# LEDDimmerI2C.net
KiCad netlist of a schematic drawn in EAGLE
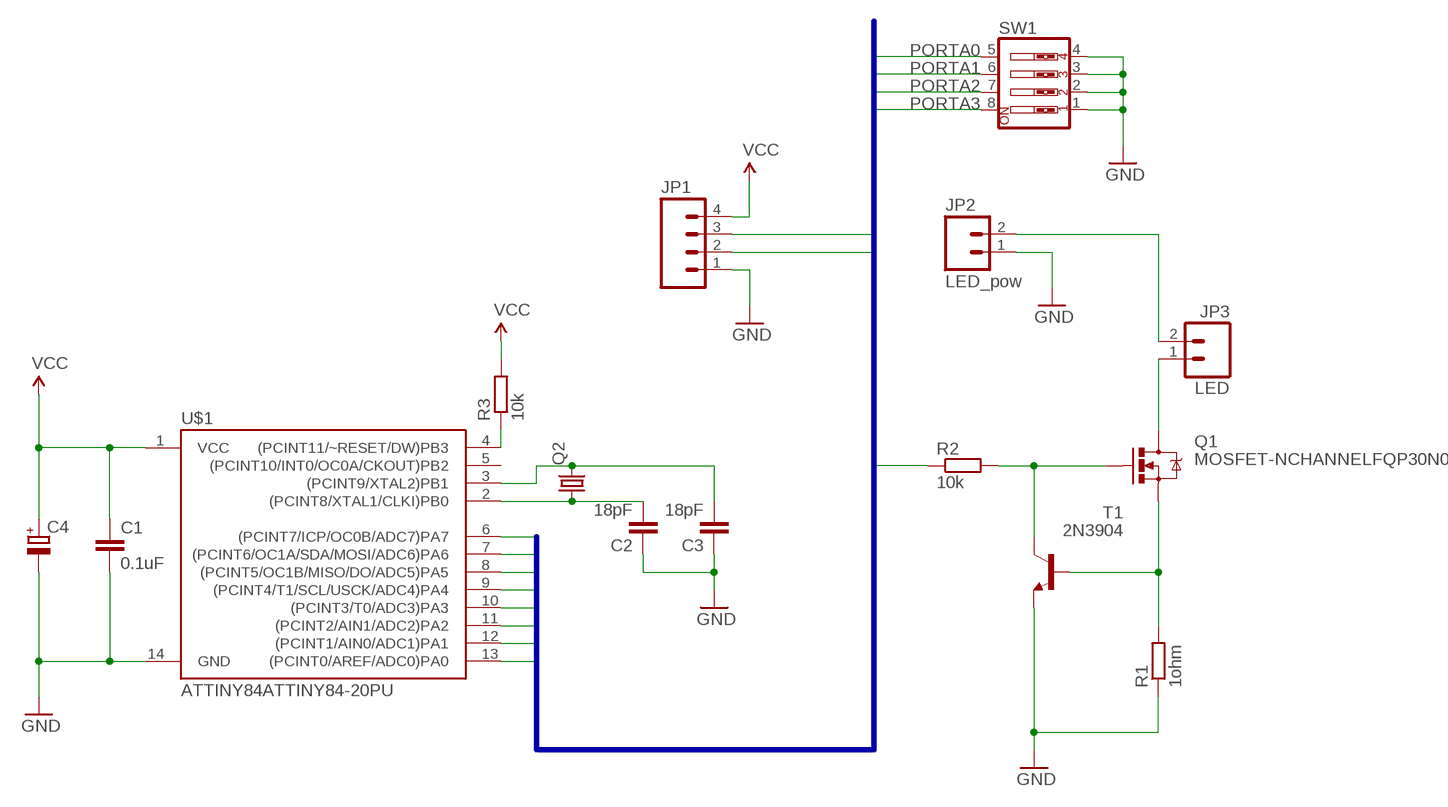
[diagram p0: schematic, sheet 1]

(export (version "E")
  (design (tool "Eeschema 10.0.6"))
  (components
    (comp (ref "C1")
      (value "0.1uF")
      (footprint "eagle-import:0805")
      (libsource (lib "eagle-import") (part "CAP0805"))
    )
    (comp (ref "C2")
      (value "18pF")
      (footprint "eagle-import:0805")
      (libsource (lib "eagle-import") (part "CAP0805"))
    )
    (comp (ref "C3")
      (value "18pF")
      (footprint "eagle-import:0805")
      (libsource (lib "eagle-import") (part "CAP0805"))
    )
    (comp (ref "C4")
      (value "CPOL-EUE3.5-10")
      (footprint "eagle-import:E3,5-10")
      (libsource (lib "eagle-import") (part "CPOL-EUE3.5-10"))
    )
    (comp (ref "JP1")
      (value "M04LONGPADS")
      (footprint "eagle-import:1X04_LONGPADS")
      (libsource (lib "eagle-import") (part "M04LONGPADS"))
    )
    (comp (ref "JP2")
      (value "LED_pow")
      (footprint "eagle-import:1X02_LONGPADS")
      (libsource (lib "eagle-import") (part "M02PTH3"))
    )
    (comp (ref "JP3")
      (value "LED")
      (footprint "eagle-import:1X02_LONGPADS")
      (libsource (lib "eagle-import") (part "M02PTH3"))
    )
    (comp (ref "Q1")
      (value "MOSFET-NCHANNELFQP30N06L")
      (footprint "eagle-import:TO220V")
      (libsource (lib "eagle-import") (part "MOSFET-NCHANNELFQP30N06L"))
    )
    (comp (ref "Q2")
      (value "CRYSTALSM49")
      (footprint "eagle-import:SM49")
      (libsource (lib "eagle-import") (part "CRYSTALSM49"))
    )
    (comp (ref "R1")
      (value "1ohm")
      (footprint "eagle-import:VMTB60")
      (libsource (lib "eagle-import") (part "R-EU_VMTB60"))
    )
    (comp (ref "R2")
      (value "10k")
      (footprint "eagle-import:R0805")
      (libsource (lib "eagle-import") (part "R-EU_R0805"))
    )
    (comp (ref "R3")
      (value "10k")
      (footprint "eagle-import:R0805")
      (libsource (lib "eagle-import") (part "R-EU_R0805"))
    )
    (comp (ref "SW1")
      (value "SW_DIP-4")
      (footprint "eagle-import:EDG-04")
      (libsource (lib "eagle-import") (part "SW_DIP-4"))
    )
    (comp (ref "T1")
      (value "2N3904")
      (footprint "eagle-import:TO92")
      (libsource (lib "eagle-import") (part "2N3904"))
    )
    (comp (ref "U$1")
      (value "ATTINY84ATTINY84-20PU")
      (footprint "eagle-import:DIL14")
      (libsource (lib "eagle-import") (part "ATTINY84ATTINY84-20PU"))
    )
  )
  (nets
    (net (code "1") (name "/PORTA0") (class "Default")
      (node (ref "SW1") (pin "5") (pinfunction "5_5") (pintype "passive"))
      (node (ref "U$1") (pin "13") (pinfunction "(PCINT0/AREF/ADC0)PA0_13") (pintype "bidirectional"))
    )
    (net (code "2") (name "/PORTA1") (class "Default")
      (node (ref "SW1") (pin "6") (pinfunction "6_6") (pintype "passive"))
      (node (ref "U$1") (pin "12") (pinfunction "(PCINT1/AIN0/ADC1)PA1_12") (pintype "bidirectional"))
    )
    (net (code "3") (name "/PORTA2") (class "Default")
      (node (ref "SW1") (pin "7") (pinfunction "7_7") (pintype "passive"))
      (node (ref "U$1") (pin "11") (pinfunction "(PCINT2/AIN1/ADC2)PA2_11") (pintype "bidirectional"))
    )
    (net (code "4") (name "/PORTA3") (class "Default")
      (node (ref "SW1") (pin "8") (pinfunction "8_8") (pintype "passive"))
      (node (ref "U$1") (pin "10") (pinfunction "(PCINT3/T0/ADC3)PA3_10") (pintype "bidirectional"))
    )
    (net (code "5") (name "/PORTA4") (class "Default")
      (node (ref "JP1") (pin "2") (pinfunction "2_2") (pintype "passive"))
      (node (ref "U$1") (pin "9") (pinfunction "(PCINT4/T1/SCL/USCK/ADC4)PA4_9") (pintype "bidirectional"))
    )
    (net (code "6") (name "/PORTA5") (class "Default")
      (node (ref "R2") (pin "1") (pinfunction "1_1") (pintype "passive"))
      (node (ref "U$1") (pin "8") (pinfunction "(PCINT5/OC1B/MISO/DO/ADC5)PA5_8") (pintype "bidirectional"))
    )
    (net (code "7") (name "/PORTA6") (class "Default")
      (node (ref "JP1") (pin "3") (pinfunction "3_3") (pintype "passive"))
      (node (ref "U$1") (pin "7") (pinfunction "(PCINT6/OC1A/SDA/MOSI/ADC6)PA6_7") (pintype "bidirectional"))
    )
    (net (code "8") (name "GND") (class "Default")
      (node (ref "C1") (pin "2") (pinfunction "2_2") (pintype "passive"))
      (node (ref "C2") (pin "1") (pinfunction "1_1") (pintype "passive"))
      (node (ref "C3") (pin "1") (pinfunction "1_1") (pintype "passive"))
      (node (ref "C4") (pin "-") (pinfunction "-_-") (pintype "passive"))
      (node (ref "JP1") (pin "1") (pinfunction "1_1") (pintype "passive"))
      (node (ref "JP2") (pin "1") (pinfunction "1_1") (pintype "passive"))
      (node (ref "R1") (pin "1") (pinfunction "1_1") (pintype "passive"))
      (node (ref "SW1") (pin "1") (pinfunction "1_1") (pintype "passive"))
      (node (ref "SW1") (pin "2") (pinfunction "2_2") (pintype "passive"))
      (node (ref "SW1") (pin "3") (pinfunction "3_3") (pintype "passive"))
      (node (ref "SW1") (pin "4") (pinfunction "4_4") (pintype "passive"))
      (node (ref "T1") (pin "3") (pinfunction "E_3") (pintype "passive"))
      (node (ref "U$1") (pin "14") (pinfunction "GND_14") (pintype "bidirectional"))
    )
    (net (code "9") (name "Net-(JP2-Pad2)") (class "Default")
      (node (ref "JP2") (pin "2") (pinfunction "2_2") (pintype "passive"))
      (node (ref "JP3") (pin "2") (pinfunction "2_2") (pintype "passive"))
    )
    (net (code "10") (name "Net-(Q1-D)") (class "Default")
      (node (ref "JP3") (pin "1") (pinfunction "1_1") (pintype "passive"))
      (node (ref "Q1") (pin "2") (pinfunction "D_2") (pintype "passive"))
    )
    (net (code "11") (name "Net-(Q1-G)") (class "Default")
      (node (ref "Q1") (pin "1") (pinfunction "G_1") (pintype "passive"))
      (node (ref "R2") (pin "2") (pinfunction "2_2") (pintype "passive"))
      (node (ref "T1") (pin "1") (pinfunction "C_1") (pintype "passive"))
    )
    (net (code "12") (name "Net-(Q1-S)") (class "Default")
      (node (ref "Q1") (pin "3") (pinfunction "S_3") (pintype "passive"))
      (node (ref "R1") (pin "2") (pinfunction "2_2") (pintype "passive"))
      (node (ref "T1") (pin "2") (pinfunction "B_2") (pintype "passive"))
    )
    (net (code "13") (name "Net-(U$1-(PCINT8{slash}XTAL1{slash}CLKI)PB0)") (class "Default")
      (node (ref "C2") (pin "2") (pinfunction "2_2") (pintype "passive"))
      (node (ref "Q2") (pin "1") (pinfunction "1_1") (pintype "passive"))
      (node (ref "U$1") (pin "2") (pinfunction "(PCINT8/XTAL1/CLKI)PB0_2") (pintype "bidirectional"))
    )
    (net (code "14") (name "Net-(U$1-(PCINT9{slash}XTAL2)PB1)") (class "Default")
      (node (ref "C3") (pin "2") (pinfunction "2_2") (pintype "passive"))
      (node (ref "Q2") (pin "2") (pinfunction "2_2") (pintype "passive"))
      (node (ref "U$1") (pin "3") (pinfunction "(PCINT9/XTAL2)PB1_3") (pintype "bidirectional"))
    )
    (net (code "15") (name "Net-(U$1-(PCINT11{slash}~{RESET{slash}DW})PB3)") (class "Default")
      (node (ref "R3") (pin "1") (pinfunction "1_1") (pintype "passive"))
      (node (ref "U$1") (pin "4") (pinfunction "(PCINT11/~{RESET/DW})PB3_4") (pintype "bidirectional"))
    )
    (net (code "16") (name "VCC") (class "Default")
      (node (ref "C1") (pin "1") (pinfunction "1_1") (pintype "passive"))
      (node (ref "C4") (pin "+") (pinfunction "+_+") (pintype "passive"))
      (node (ref "JP1") (pin "4") (pinfunction "4_4") (pintype "passive"))
      (node (ref "R3") (pin "2") (pinfunction "2_2") (pintype "passive"))
      (node (ref "U$1") (pin "1") (pinfunction "VCC_1") (pintype "bidirectional"))
    )
    (net (code "17") (name "unconnected-(U$1-(PCINT7{slash}ICP{slash}OC0B{slash}ADC7)PA7-Pad6)") (class "Default")
      (node (ref "U$1") (pin "6") (pinfunction "(PCINT7/ICP/OC0B/ADC7)PA7_6") (pintype "bidirectional"))
    )
    (net (code "18") (name "unconnected-(U$1-(PCINT10{slash}INT0{slash}OC0A{slash}CKOUT)PB2-Pad5)") (class "Default")
      (node (ref "U$1") (pin "5") (pinfunction "(PCINT10/INT0/OC0A/CKOUT)PB2_5") (pintype "bidirectional"))
    )
  )
)
